# Amplifier-Speaker.net
KiCad netlist of a schematic drawn in Altium Designer
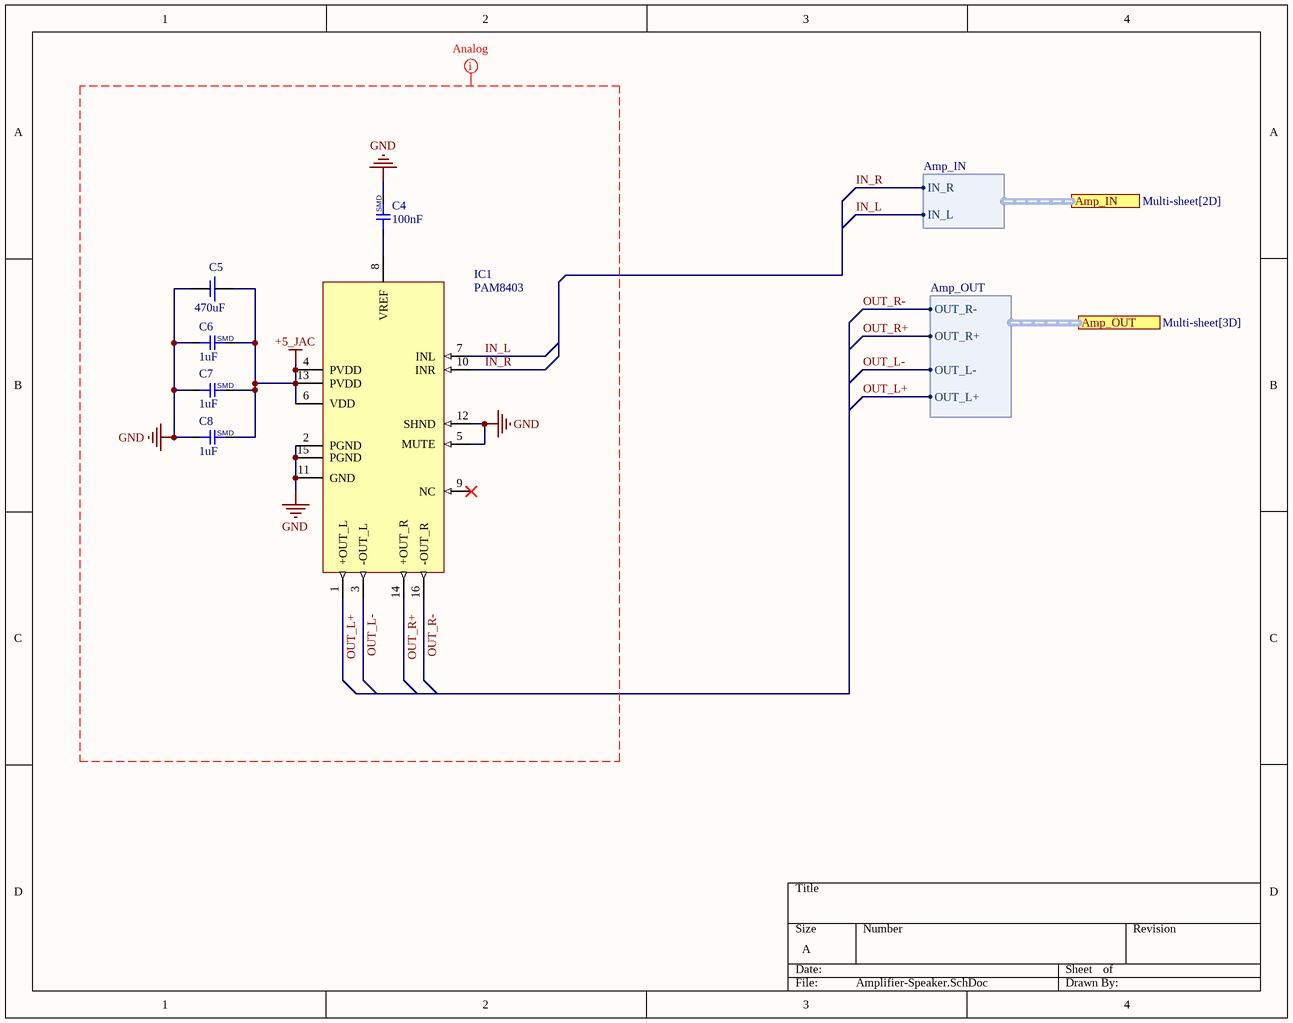
[diagram p0: Amplifier-Speaker.SchDoc]

(export (version "E")
  (design (tool "Eeschema 10.0.6"))
  (components
    (comp (ref "C4") (value "100nF") (footprint "CAP-0603") (libsource (lib "kave-eng-pro") (part "cap_smd")))
    (comp (ref "C5")
      (value "470uF")
      (footprint "cap/330u/16v")
      (libsource (lib "kave-eng-pro") (part "cap-electrolit"))
    )
    (comp (ref "C6") (value "1uF") (footprint "CAP-0805") (libsource (lib "kave-eng-pro") (part "cap_smd")))
    (comp (ref "C7") (value "1uF") (footprint "CAP-0805") (libsource (lib "kave-eng-pro") (part "cap_smd")))
    (comp (ref "C8") (value "1uF") (footprint "CAP-0805") (libsource (lib "kave-eng-pro") (part "cap_smd")))
    (comp (ref "IC1")
      (value "PAM8403")
      (footprint "SOP16")
      (description "STEREO AUDIO AMPLIFIER")
      (libsource (lib "kave-eng-pro") (part "PAM8403"))
    )
  )
  (nets
    (net (code "3") (name "+5_JAC") (class "Default")
      (node (ref "C5") (pin "+") (pintype "passive"))
      (node (ref "C6") (pin "2") (pintype "passive"))
      (node (ref "C7") (pin "2") (pintype "passive"))
      (node (ref "C8") (pin "2") (pintype "passive"))
      (node (ref "IC1") (pin "13") (pinfunction "PVDD_13") (pintype "power_in"))
      (node (ref "IC1") (pin "4") (pinfunction "PVDD_4") (pintype "power_in"))
      (node (ref "IC1") (pin "6") (pinfunction "VDD_6") (pintype "power_in"))
    )
    (net (code "4") (name "/IN_L") (class "Default")
      (node (ref "IC1") (pin "7") (pinfunction "INL_7") (pintype "input"))
    )
    (net (code "5") (name "/IN_R") (class "Default")
      (node (ref "IC1") (pin "10") (pinfunction "INR_10") (pintype "input"))
    )
    (net (code "6") (name "/OUT_L+") (class "Default")
      (node (ref "IC1") (pin "1") (pinfunction "+OUT_L_1") (pintype "output"))
    )
    (net (code "7") (name "/OUT_L-") (class "Default")
      (node (ref "IC1") (pin "3") (pinfunction "-OUT_L_3") (pintype "output"))
    )
    (net (code "8") (name "/OUT_R+") (class "Default")
      (node (ref "IC1") (pin "14") (pinfunction "+OUT_R_14") (pintype "output"))
    )
    (net (code "9") (name "/OUT_R-") (class "Default")
      (node (ref "IC1") (pin "16") (pinfunction "-OUT_R_16") (pintype "output"))
    )
    (net (code "12") (name "GND") (class "Default")
      (node (ref "C4") (pin "2") (pintype "passive"))
      (node (ref "C5") (pin "-") (pintype "passive"))
      (node (ref "C6") (pin "1") (pintype "passive"))
      (node (ref "C7") (pin "1") (pintype "passive"))
      (node (ref "C8") (pin "1") (pintype "passive"))
      (node (ref "IC1") (pin "11") (pinfunction "GND_11") (pintype "power_in"))
      (node (ref "IC1") (pin "12") (pinfunction "SHND_12") (pintype "input"))
      (node (ref "IC1") (pin "15") (pinfunction "PGND_15") (pintype "power_in"))
      (node (ref "IC1") (pin "2") (pinfunction "PGND_2") (pintype "power_in"))
      (node (ref "IC1") (pin "5") (pinfunction "MUTE_5") (pintype "input"))
    )
    (net (code "13") (name "Net-(IC1-VREF)") (class "Default")
      (node (ref "C4") (pin "1") (pintype "passive"))
      (node (ref "IC1") (pin "8") (pinfunction "VREF_8") (pintype "power_in"))
    )
    (net (code "14") (name "unconnected-(IC1-NC-Pad9)") (class "Default")
      (node (ref "IC1") (pin "9") (pinfunction "NC_9") (pintype "input+no_connect"))
    )
  )
)
